# DSP_R.net
KiCad netlist of a schematic drawn in Altium Designer
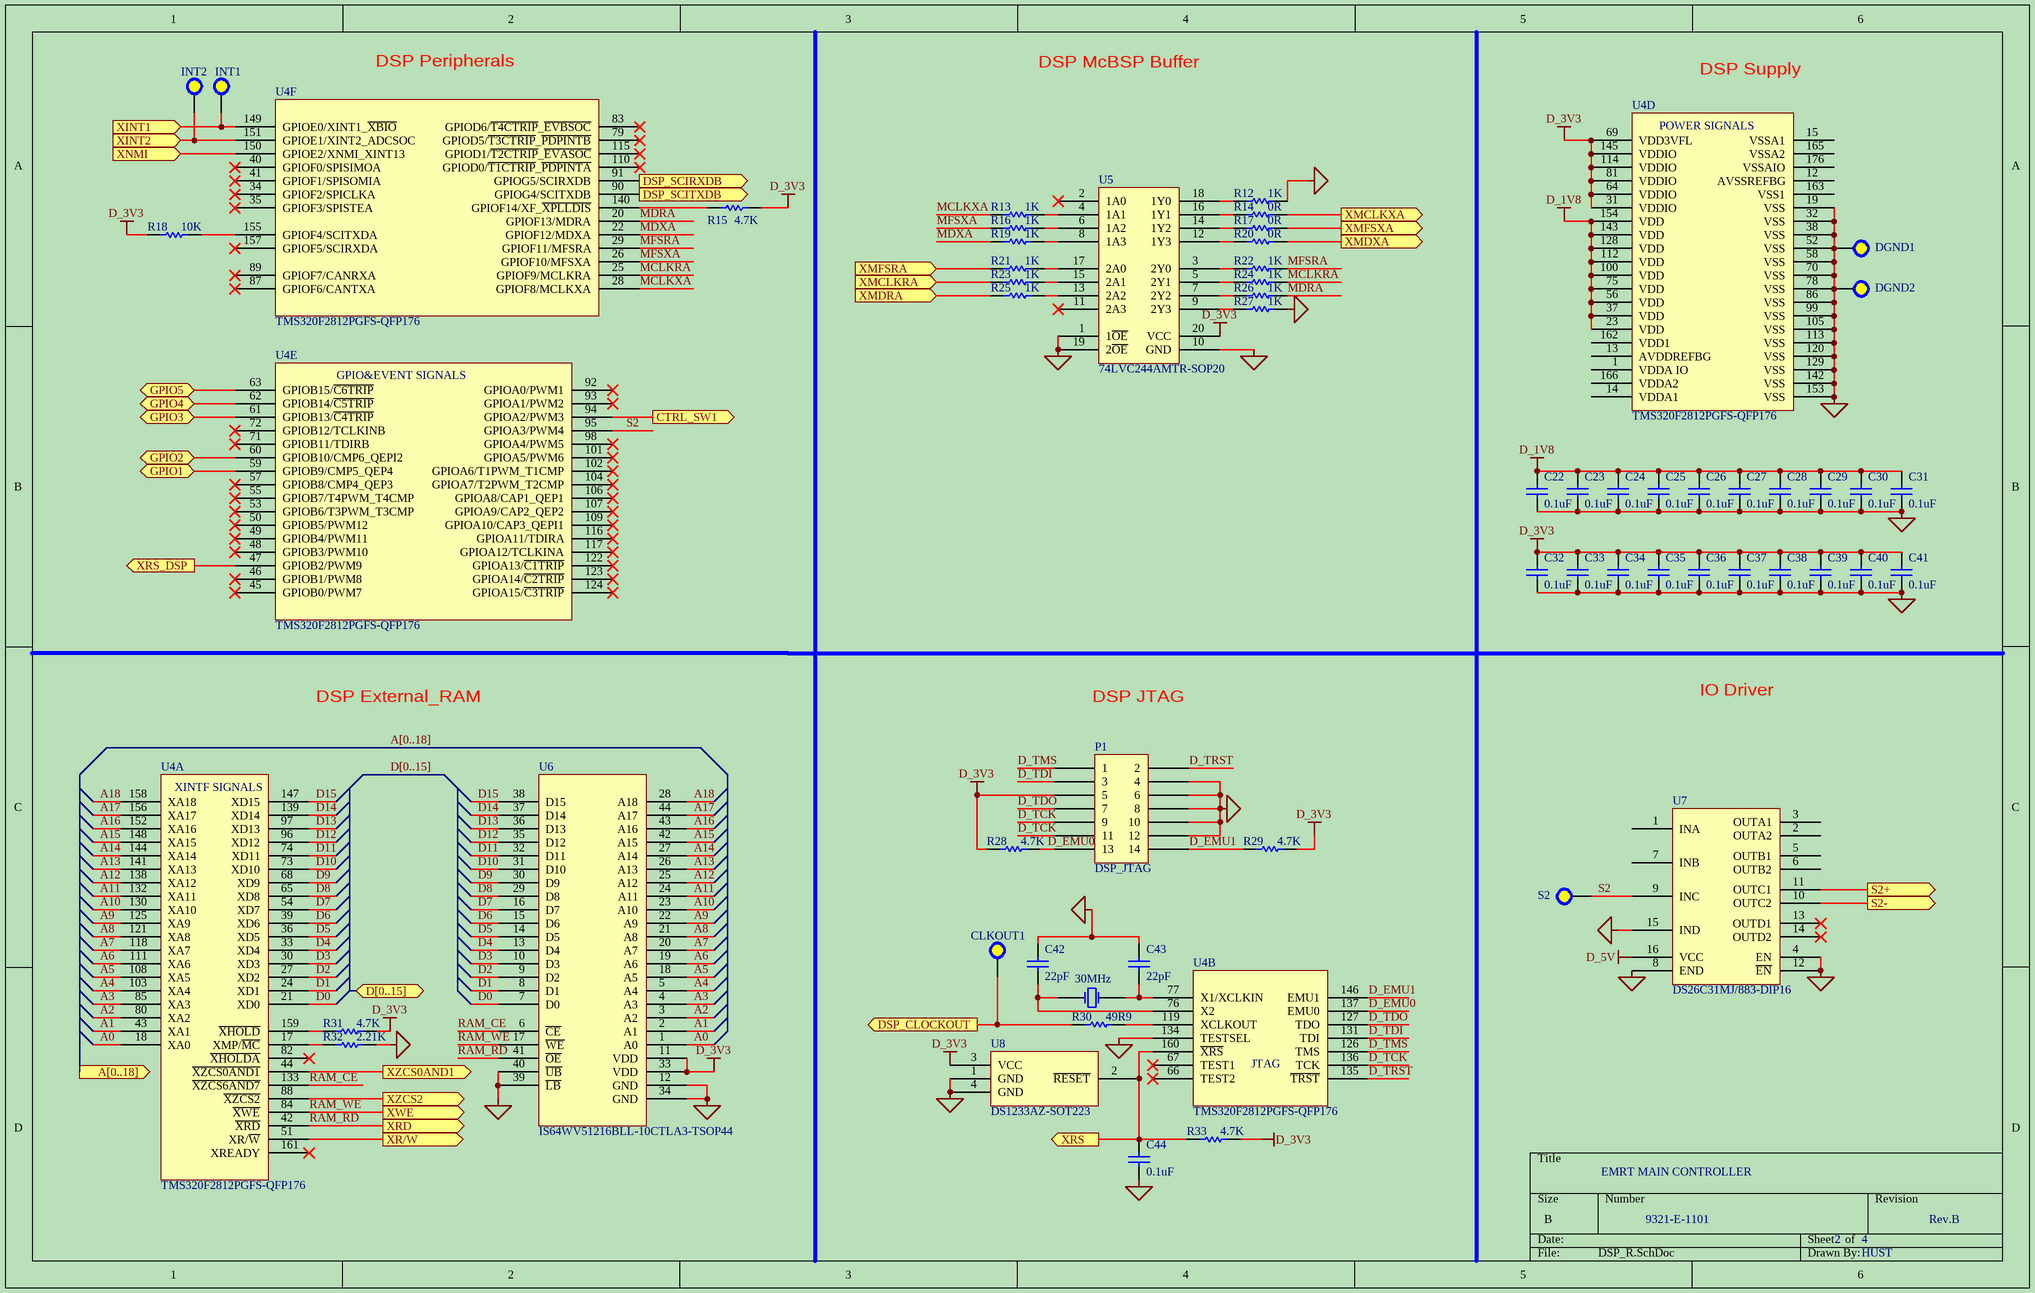
[diagram p0: DSP_R.SchDoc]

(export (version "E")
  (design (tool "Eeschema 10.0.6"))
  (components
    (comp (ref "C22")
      (value "0.1uF")
      (footprint "CAPS0805_57")
      (description "Capacitor")
      (fields (field (name "PART NUMBER") "Y20025084") (field (name "Comment") "Cap"))
      (libsource (lib "Cap") (part "Cap"))
    )
    (comp (ref "C23")
      (value "0.1uF")
      (footprint "CAPS0805_57")
      (description "Capacitor")
      (fields (field (name "PART NUMBER") "Y20025084") (field (name "Comment") "Cap"))
      (libsource (lib "Cap") (part "Cap"))
    )
    (comp (ref "C24")
      (value "0.1uF")
      (footprint "CAPS0805_57")
      (description "Capacitor")
      (fields (field (name "PART NUMBER") "Y20025084") (field (name "Comment") "Cap"))
      (libsource (lib "Cap") (part "Cap"))
    )
    (comp (ref "C25")
      (value "0.1uF")
      (footprint "CAPS0805_57")
      (description "Capacitor")
      (fields (field (name "PART NUMBER") "Y20025084") (field (name "Comment") "Cap"))
      (libsource (lib "Cap") (part "Cap"))
    )
    (comp (ref "C26")
      (value "0.1uF")
      (footprint "CAPS0805_57")
      (description "Capacitor")
      (fields (field (name "PART NUMBER") "Y20025084") (field (name "Comment") "Cap"))
      (libsource (lib "Cap") (part "Cap"))
    )
    (comp (ref "C27")
      (value "0.1uF")
      (footprint "CAPS0805_57")
      (description "Capacitor")
      (fields (field (name "PART NUMBER") "Y20025084") (field (name "Comment") "Cap"))
      (libsource (lib "Cap") (part "Cap"))
    )
    (comp (ref "C28")
      (value "0.1uF")
      (footprint "CAPS0805_57")
      (description "Capacitor")
      (fields (field (name "PART NUMBER") "Y20025084") (field (name "Comment") "Cap"))
      (libsource (lib "Cap") (part "Cap"))
    )
    (comp (ref "C29")
      (value "0.1uF")
      (footprint "CAPS0805_57")
      (description "Capacitor")
      (fields (field (name "PART NUMBER") "Y20025084") (field (name "Comment") "Cap"))
      (libsource (lib "Cap") (part "Cap"))
    )
    (comp (ref "C30")
      (value "0.1uF")
      (footprint "CAPS0805_57")
      (description "Capacitor")
      (fields (field (name "PART NUMBER") "Y20025084") (field (name "Comment") "Cap"))
      (libsource (lib "Cap") (part "Cap"))
    )
    (comp (ref "C31")
      (value "0.1uF")
      (footprint "CAPS0805_57")
      (description "Capacitor")
      (fields (field (name "PART NUMBER") "Y20025084") (field (name "Comment") "Cap"))
      (libsource (lib "Cap") (part "Cap"))
    )
    (comp (ref "C32")
      (value "0.1uF")
      (footprint "CAPS0805_57")
      (description "Capacitor")
      (fields (field (name "PART NUMBER") "Y20025084") (field (name "Comment") "Cap"))
      (libsource (lib "Cap") (part "Cap"))
    )
    (comp (ref "C33")
      (value "0.1uF")
      (footprint "CAPS0805_57")
      (description "Capacitor")
      (fields (field (name "PART NUMBER") "Y20025084") (field (name "Comment") "Cap"))
      (libsource (lib "Cap") (part "Cap"))
    )
    (comp (ref "C34")
      (value "0.1uF")
      (footprint "CAPS0805_57")
      (description "Capacitor")
      (fields (field (name "PART NUMBER") "Y20025084") (field (name "Comment") "Cap"))
      (libsource (lib "Cap") (part "Cap"))
    )
    (comp (ref "C35")
      (value "0.1uF")
      (footprint "CAPS0805_57")
      (description "Capacitor")
      (fields (field (name "PART NUMBER") "Y20025084") (field (name "Comment") "Cap"))
      (libsource (lib "Cap") (part "Cap"))
    )
    (comp (ref "C36")
      (value "0.1uF")
      (footprint "CAPS0805_57")
      (description "Capacitor")
      (fields (field (name "PART NUMBER") "Y20025084") (field (name "Comment") "Cap"))
      (libsource (lib "Cap") (part "Cap"))
    )
    (comp (ref "C37")
      (value "0.1uF")
      (footprint "CAPS0805_57")
      (description "Capacitor")
      (fields (field (name "PART NUMBER") "Y20025084") (field (name "Comment") "Cap"))
      (libsource (lib "Cap") (part "Cap"))
    )
    (comp (ref "C38")
      (value "0.1uF")
      (footprint "CAPS0805_57")
      (description "Capacitor")
      (fields (field (name "PART NUMBER") "Y20025084") (field (name "Comment") "Cap"))
      (libsource (lib "Cap") (part "Cap"))
    )
    (comp (ref "C39")
      (value "0.1uF")
      (footprint "CAPS0805_57")
      (description "Capacitor")
      (fields (field (name "PART NUMBER") "Y20025084") (field (name "Comment") "Cap"))
      (libsource (lib "Cap") (part "Cap"))
    )
    (comp (ref "C40")
      (value "0.1uF")
      (footprint "CAPS0805_57")
      (description "Capacitor")
      (fields (field (name "PART NUMBER") "Y20025084") (field (name "Comment") "Cap"))
      (libsource (lib "Cap") (part "Cap"))
    )
    (comp (ref "C41")
      (value "0.1uF")
      (footprint "CAPS0805_57")
      (description "Capacitor")
      (fields (field (name "PART NUMBER") "Y20025084") (field (name "Comment") "Cap"))
      (libsource (lib "Cap") (part "Cap"))
    )
    (comp (ref "C42")
      (value "22pF")
      (footprint "CAPS0805_57")
      (description "Capacitor")
      (fields (field (name "PART NUMBER") "Y20025084") (field (name "Comment") "Cap"))
      (libsource (lib "Cap") (part "Cap"))
    )
    (comp (ref "C43")
      (value "22pF")
      (footprint "CAPS0805_57")
      (description "Capacitor")
      (fields (field (name "PART NUMBER") "Y20025084") (field (name "Comment") "Cap"))
      (libsource (lib "Cap") (part "Cap"))
    )
    (comp (ref "C44")
      (value "0.1uF")
      (footprint "CAPS0805_57")
      (description "Capacitor")
      (fields (field (name "PART NUMBER") "Y20025084") (field (name "Comment") "Cap"))
      (libsource (lib "Cap") (part "Cap"))
    )
    (comp (ref "CLKOUT1")
      (value "TEST_SMALL")
      (footprint "test_small")
      (libsource (lib "srj") (part "TEST_SMALL"))
    )
    (comp (ref "DGND1")
      (value "TST_LARGE")
      (footprint "test_large")
      (libsource (lib "srj") (part "TEST_LARGE"))
    )
    (comp (ref "DGND2")
      (value "TST_LARGE")
      (footprint "test_large")
      (libsource (lib "srj") (part "TEST_LARGE"))
    )
    (comp (ref "INT1")
      (value "TEST_SMALL")
      (footprint "test_small")
      (libsource (lib "srj") (part "TEST_SMALL"))
    )
    (comp (ref "INT2")
      (value "TEST_SMALL")
      (footprint "test_small")
      (libsource (lib "srj") (part "TEST_SMALL"))
    )
    (comp (ref "P1")
      (value "DSP_JTAG")
      (footprint "HDR2X7")
      (libsource (lib "MainController-HT") (part "DSP_JTAG"))
    )
    (comp (ref "R12")
      (value "1K")
      (footprint "RESS0805")
      (description "Semiconductor Resistor")
      (fields
        (field (name "MANUFACTURER") "Generic Components")
        (field (name "Comment") "Res")
        (field (name "PUBLISHER") "Altium Hobart Technology Centre")
      )
      (libsource (lib "EMRT MAIN CONTROLLER") (part "Res"))
    )
    (comp (ref "R13")
      (value "1K")
      (footprint "RESS0805")
      (description "Semiconductor Resistor")
      (fields
        (field (name "MANUFACTURER") "Generic Components")
        (field (name "Comment") "Res")
        (field (name "PUBLISHER") "Altium Hobart Technology Centre")
      )
      (libsource (lib "EMRT MAIN CONTROLLER") (part "Res"))
    )
    (comp (ref "R14")
      (value "0R")
      (footprint "RESS0805")
      (description "Semiconductor Resistor")
      (fields
        (field (name "MANUFACTURER") "Generic Components")
        (field (name "Comment") "Res")
        (field (name "PUBLISHER") "Altium Hobart Technology Centre")
      )
      (libsource (lib "EMRT MAIN CONTROLLER") (part "Res"))
    )
    (comp (ref "R15")
      (value "4.7K")
      (footprint "RESS0805")
      (description "Semiconductor Resistor")
      (fields
        (field (name "MANUFACTURER") "Generic Components")
        (field (name "Comment") "Res")
        (field (name "PUBLISHER") "Altium Hobart Technology Centre")
      )
      (libsource (lib "EMRT MAIN CONTROLLER") (part "Res"))
    )
    (comp (ref "R16")
      (value "1K")
      (footprint "RESS0805")
      (description "Semiconductor Resistor")
      (fields
        (field (name "MANUFACTURER") "Generic Components")
        (field (name "Comment") "Res")
        (field (name "PUBLISHER") "Altium Hobart Technology Centre")
      )
      (libsource (lib "EMRT MAIN CONTROLLER") (part "Res"))
    )
    (comp (ref "R17")
      (value "0R")
      (footprint "RESS0805")
      (description "Semiconductor Resistor")
      (fields
        (field (name "MANUFACTURER") "Generic Components")
        (field (name "Comment") "Res")
        (field (name "PUBLISHER") "Altium Hobart Technology Centre")
      )
      (libsource (lib "EMRT MAIN CONTROLLER") (part "Res"))
    )
    (comp (ref "R18")
      (value "10K")
      (footprint "RESS0805")
      (description "Semiconductor Resistor")
      (fields
        (field (name "MANUFACTURER") "Generic Components")
        (field (name "Comment") "Res")
        (field (name "PUBLISHER") "Altium Hobart Technology Centre")
      )
      (libsource (lib "EMRT MAIN CONTROLLER") (part "Res"))
    )
    (comp (ref "R19")
      (value "1K")
      (footprint "RESS0805")
      (description "Semiconductor Resistor")
      (fields
        (field (name "MANUFACTURER") "Generic Components")
        (field (name "Comment") "Res")
        (field (name "PUBLISHER") "Altium Hobart Technology Centre")
      )
      (libsource (lib "EMRT MAIN CONTROLLER") (part "Res"))
    )
    (comp (ref "R20")
      (value "0R")
      (footprint "RESS0805")
      (description "Semiconductor Resistor")
      (fields
        (field (name "MANUFACTURER") "Generic Components")
        (field (name "Comment") "Res")
        (field (name "PUBLISHER") "Altium Hobart Technology Centre")
      )
      (libsource (lib "EMRT MAIN CONTROLLER") (part "Res"))
    )
    (comp (ref "R21")
      (value "1K")
      (footprint "RESS0805")
      (description "Semiconductor Resistor")
      (fields
        (field (name "MANUFACTURER") "Generic Components")
        (field (name "Comment") "Res")
        (field (name "PUBLISHER") "Altium Hobart Technology Centre")
      )
      (libsource (lib "EMRT MAIN CONTROLLER") (part "Res"))
    )
    (comp (ref "R22")
      (value "1K")
      (footprint "RESS0805")
      (description "Semiconductor Resistor")
      (fields
        (field (name "MANUFACTURER") "Generic Components")
        (field (name "Comment") "Res")
        (field (name "PUBLISHER") "Altium Hobart Technology Centre")
      )
      (libsource (lib "EMRT MAIN CONTROLLER") (part "Res"))
    )
    (comp (ref "R23")
      (value "1K")
      (footprint "RESS0805")
      (description "Semiconductor Resistor")
      (fields
        (field (name "MANUFACTURER") "Generic Components")
        (field (name "Comment") "Res")
        (field (name "PUBLISHER") "Altium Hobart Technology Centre")
      )
      (libsource (lib "EMRT MAIN CONTROLLER") (part "Res"))
    )
    (comp (ref "R24")
      (value "1K")
      (footprint "RESS0805")
      (description "Semiconductor Resistor")
      (fields
        (field (name "MANUFACTURER") "Generic Components")
        (field (name "Comment") "Res")
        (field (name "PUBLISHER") "Altium Hobart Technology Centre")
      )
      (libsource (lib "EMRT MAIN CONTROLLER") (part "Res"))
    )
    (comp (ref "R25")
      (value "1K")
      (footprint "RESS0805")
      (description "Semiconductor Resistor")
      (fields
        (field (name "MANUFACTURER") "Generic Components")
        (field (name "Comment") "Res")
        (field (name "PUBLISHER") "Altium Hobart Technology Centre")
      )
      (libsource (lib "EMRT MAIN CONTROLLER") (part "Res"))
    )
    (comp (ref "R26")
      (value "1K")
      (footprint "RESS0805")
      (description "Semiconductor Resistor")
      (fields
        (field (name "MANUFACTURER") "Generic Components")
        (field (name "Comment") "Res")
        (field (name "PUBLISHER") "Altium Hobart Technology Centre")
      )
      (libsource (lib "EMRT MAIN CONTROLLER") (part "Res"))
    )
    (comp (ref "R27")
      (value "1K")
      (footprint "RESS0805")
      (description "Semiconductor Resistor")
      (fields
        (field (name "MANUFACTURER") "Generic Components")
        (field (name "Comment") "Res")
        (field (name "PUBLISHER") "Altium Hobart Technology Centre")
      )
      (libsource (lib "EMRT MAIN CONTROLLER") (part "Res"))
    )
    (comp (ref "R28")
      (value "4.7K")
      (footprint "RESS0805")
      (description "Semiconductor Resistor")
      (fields
        (field (name "MANUFACTURER") "Generic Components")
        (field (name "Comment") "Res")
        (field (name "PUBLISHER") "Altium Hobart Technology Centre")
      )
      (libsource (lib "EMRT MAIN CONTROLLER") (part "Res"))
    )
    (comp (ref "R29")
      (value "4.7K")
      (footprint "RESS0805")
      (description "Semiconductor Resistor")
      (fields
        (field (name "MANUFACTURER") "Generic Components")
        (field (name "Comment") "Res")
        (field (name "PUBLISHER") "Altium Hobart Technology Centre")
      )
      (libsource (lib "EMRT MAIN CONTROLLER") (part "Res"))
    )
    (comp (ref "R30")
      (value "49R9")
      (footprint "RESS0805")
      (description "Semiconductor Resistor")
      (fields
        (field (name "MANUFACTURER") "Generic Components")
        (field (name "Comment") "Res")
        (field (name "PUBLISHER") "Altium Hobart Technology Centre")
      )
      (libsource (lib "EMRT MAIN CONTROLLER") (part "Res"))
    )
    (comp (ref "R31")
      (value "4.7K")
      (footprint "RESS0805")
      (description "Semiconductor Resistor")
      (fields
        (field (name "MANUFACTURER") "Generic Components")
        (field (name "Comment") "Res")
        (field (name "PUBLISHER") "Altium Hobart Technology Centre")
      )
      (libsource (lib "EMRT MAIN CONTROLLER") (part "Res"))
    )
    (comp (ref "R32")
      (value "2.21K")
      (footprint "RESS0805")
      (description "Semiconductor Resistor")
      (fields
        (field (name "MANUFACTURER") "Generic Components")
        (field (name "Comment") "Res")
        (field (name "PUBLISHER") "Altium Hobart Technology Centre")
      )
      (libsource (lib "EMRT MAIN CONTROLLER") (part "Res"))
    )
    (comp (ref "R33")
      (value "4.7K")
      (footprint "RESS0805")
      (description "Semiconductor Resistor")
      (fields
        (field (name "MANUFACTURER") "Generic Components")
        (field (name "Comment") "Res")
        (field (name "PUBLISHER") "Altium Hobart Technology Centre")
      )
      (libsource (lib "EMRT MAIN CONTROLLER") (part "Res"))
    )
    (comp (ref "S2") (value "TST_LARGE") (footprint "test_large") (libsource (lib "srj") (part "TEST_LARGE")))
    (comp (ref "U4")
      (value "TMS320F2812PGFS-QFP176")
      (footprint "QFP176")
      (libsource (lib "srj") (part "TMS320F2812(176PIN)"))
    )
    (comp (ref "U5")
      (value "74LVC244AMTR-SOP20")
      (footprint "B-PDSO_20q1280×1030×265_p127")
      (libsource (lib "srj") (part "74LVC244AMTR"))
    )
    (comp (ref "U6")
      (value "IS64WV51216BLL-10CTLA3-TSOP44")
      (footprint "TSOP44")
      (libsource (lib "srj") (part "IS61LV51216"))
    )
    (comp (ref "U7")
      (value "DS26C31MJ/883-DIP16")
      (footprint "CDIP_16q785×305×200_d18_p100_i300")
      (libsource (lib "srj") (part "DS26LVC31"))
    )
    (comp (ref "U8")
      (value "DS1233AZ-SOT223")
      (footprint "PDSO_3q700×650×180_p230")
      (libsource (lib "srj") (part "DS1233AZ-15"))
    )
    (comp (ref "Y1")
      (value "XTAL")
      (footprint "XTALBCY_2q311×126×236_d13_p150")
      (description "Crystal Oscillator")
      (fields (field (name "ALTIUM_UNNAMED_1") "30MHz") (field (name "PUBLISHER") "Altium Limited"))
      (libsource (lib "Miscellaneous Devices") (part "XTAL"))
    )
  )
  (nets
    (net (code "1") (name "/A0") (class "Default")
      (node (ref "U4") (pin "18") (pinfunction "XA0_18") (pintype "passive"))
      (node (ref "U6") (pin "1") (pinfunction "A0_1") (pintype "passive"))
    )
    (net (code "2") (name "/A1") (class "Default")
      (node (ref "U4") (pin "43") (pinfunction "XA1_43") (pintype "passive"))
      (node (ref "U6") (pin "2") (pinfunction "A1_2") (pintype "passive"))
    )
    (net (code "3") (name "/A2") (class "Default")
      (node (ref "U4") (pin "80") (pinfunction "XA2_80") (pintype "passive"))
      (node (ref "U6") (pin "3") (pinfunction "A2_3") (pintype "passive"))
    )
    (net (code "4") (name "/A3") (class "Default")
      (node (ref "U4") (pin "85") (pinfunction "XA3_85") (pintype "passive"))
      (node (ref "U6") (pin "4") (pinfunction "A3_4") (pintype "passive"))
    )
    (net (code "5") (name "/A4") (class "Default")
      (node (ref "U4") (pin "103") (pinfunction "XA4_103") (pintype "passive"))
      (node (ref "U6") (pin "5") (pinfunction "A4_5") (pintype "passive"))
    )
    (net (code "6") (name "/A5") (class "Default")
      (node (ref "U4") (pin "108") (pinfunction "XA5_108") (pintype "passive"))
      (node (ref "U6") (pin "18") (pinfunction "A5_18") (pintype "passive"))
    )
    (net (code "7") (name "/A6") (class "Default")
      (node (ref "U4") (pin "111") (pinfunction "XA6_111") (pintype "passive"))
      (node (ref "U6") (pin "19") (pinfunction "A6_19") (pintype "passive"))
    )
    (net (code "8") (name "/A7") (class "Default")
      (node (ref "U4") (pin "118") (pinfunction "XA7_118") (pintype "passive"))
      (node (ref "U6") (pin "20") (pinfunction "A7_20") (pintype "passive"))
    )
    (net (code "9") (name "/A8") (class "Default")
      (node (ref "U4") (pin "121") (pinfunction "XA8_121") (pintype "passive"))
      (node (ref "U6") (pin "21") (pinfunction "A8_21") (pintype "passive"))
    )
    (net (code "10") (name "/A9") (class "Default")
      (node (ref "U4") (pin "125") (pinfunction "XA9_125") (pintype "passive"))
      (node (ref "U6") (pin "22") (pinfunction "A9_22") (pintype "passive"))
    )
    (net (code "11") (name "/A10") (class "Default")
      (node (ref "U4") (pin "130") (pinfunction "XA10_130") (pintype "passive"))
      (node (ref "U6") (pin "23") (pinfunction "A10_23") (pintype "passive"))
    )
    (net (code "12") (name "/A11") (class "Default")
      (node (ref "U4") (pin "132") (pinfunction "XA11_132") (pintype "passive"))
      (node (ref "U6") (pin "24") (pinfunction "A11_24") (pintype "passive"))
    )
    (net (code "13") (name "/A12") (class "Default")
      (node (ref "U4") (pin "138") (pinfunction "XA12_138") (pintype "passive"))
      (node (ref "U6") (pin "25") (pinfunction "A12_25") (pintype "passive"))
    )
    (net (code "14") (name "/A13") (class "Default")
      (node (ref "U4") (pin "141") (pinfunction "XA13_141") (pintype "passive"))
      (node (ref "U6") (pin "26") (pinfunction "A13_26") (pintype "passive"))
    )
    (net (code "15") (name "/A14") (class "Default")
      (node (ref "U4") (pin "144") (pinfunction "XA14_144") (pintype "passive"))
      (node (ref "U6") (pin "27") (pinfunction "A14_27") (pintype "passive"))
    )
    (net (code "16") (name "/A15") (class "Default")
      (node (ref "U4") (pin "148") (pinfunction "XA15_148") (pintype "passive"))
      (node (ref "U6") (pin "42") (pinfunction "A15_42") (pintype "passive"))
    )
    (net (code "17") (name "/A16") (class "Default")
      (node (ref "U4") (pin "152") (pinfunction "XA16_152") (pintype "passive"))
      (node (ref "U6") (pin "43") (pinfunction "A16_43") (pintype "passive"))
    )
    (net (code "18") (name "/A17") (class "Default")
      (node (ref "U4") (pin "156") (pinfunction "XA17_156") (pintype "passive"))
      (node (ref "U6") (pin "44") (pinfunction "A17_44") (pintype "passive"))
    )
    (net (code "19") (name "/A18") (class "Default")
      (node (ref "U4") (pin "158") (pinfunction "XA18_158") (pintype "passive"))
      (node (ref "U6") (pin "28") (pinfunction "A18_28") (pintype "passive"))
    )
    (net (code "21") (name "/CTRL_SW1") (class "Default")
      (node (ref "U4") (pin "94") (pinfunction "GPIOA2/PWM3_94") (pintype "passive"))
    )
    (net (code "22") (name "/D0") (class "Default")
      (node (ref "U4") (pin "21") (pinfunction "XD0_21") (pintype "passive"))
      (node (ref "U6") (pin "7") (pinfunction "D0_7") (pintype "passive"))
    )
    (net (code "23") (name "/D1") (class "Default")
      (node (ref "U4") (pin "24") (pinfunction "XD1_24") (pintype "passive"))
      (node (ref "U6") (pin "8") (pinfunction "D1_8") (pintype "passive"))
    )
    (net (code "24") (name "/D2") (class "Default")
      (node (ref "U4") (pin "27") (pinfunction "XD2_27") (pintype "passive"))
      (node (ref "U6") (pin "9") (pinfunction "D2_9") (pintype "passive"))
    )
    (net (code "25") (name "/D3") (class "Default")
      (node (ref "U4") (pin "30") (pinfunction "XD3_30") (pintype "passive"))
      (node (ref "U6") (pin "10") (pinfunction "D3_10") (pintype "passive"))
    )
    (net (code "26") (name "/D4") (class "Default")
      (node (ref "U4") (pin "33") (pinfunction "XD4_33") (pintype "passive"))
      (node (ref "U6") (pin "13") (pinfunction "D4_13") (pintype "passive"))
    )
    (net (code "27") (name "/D5") (class "Default")
      (node (ref "U4") (pin "36") (pinfunction "XD5_36") (pintype "passive"))
      (node (ref "U6") (pin "14") (pinfunction "D5_14") (pintype "passive"))
    )
    (net (code "28") (name "/D6") (class "Default")
      (node (ref "U4") (pin "39") (pinfunction "XD6_39") (pintype "passive"))
      (node (ref "U6") (pin "15") (pinfunction "D6_15") (pintype "passive"))
    )
    (net (code "29") (name "/D7") (class "Default")
      (node (ref "U4") (pin "54") (pinfunction "XD7_54") (pintype "passive"))
      (node (ref "U6") (pin "16") (pinfunction "D7_16") (pintype "passive"))
    )
    (net (code "30") (name "/D8") (class "Default")
      (node (ref "U4") (pin "65") (pinfunction "XD8_65") (pintype "passive"))
      (node (ref "U6") (pin "29") (pinfunction "D8_29") (pintype "passive"))
    )
    (net (code "31") (name "/D9") (class "Default")
      (node (ref "U4") (pin "68") (pinfunction "XD9_68") (pintype "passive"))
      (node (ref "U6") (pin "30") (pinfunction "D9_30") (pintype "passive"))
    )
    (net (code "32") (name "/D10") (class "Default")
      (node (ref "U4") (pin "73") (pinfunction "XD10_73") (pintype "passive"))
      (node (ref "U6") (pin "31") (pinfunction "D10_31") (pintype "passive"))
    )
    (net (code "33") (name "/D11") (class "Default")
      (node (ref "U4") (pin "74") (pinfunction "XD11_74") (pintype "passive"))
      (node (ref "U6") (pin "32") (pinfunction "D11_32") (pintype "passive"))
    )
    (net (code "34") (name "/D12") (class "Default")
      (node (ref "U4") (pin "96") (pinfunction "XD12_96") (pintype "passive"))
      (node (ref "U6") (pin "35") (pinfunction "D12_35") (pintype "passive"))
    )
    (net (code "35") (name "/D13") (class "Default")
      (node (ref "U4") (pin "97") (pinfunction "XD13_97") (pintype "passive"))
      (node (ref "U6") (pin "36") (pinfunction "D13_36") (pintype "passive"))
    )
    (net (code "36") (name "/D14") (class "Default")
      (node (ref "U4") (pin "139") (pinfunction "XD14_139") (pintype "passive"))
      (node (ref "U6") (pin "37") (pinfunction "D14_37") (pintype "passive"))
    )
    (net (code "37") (name "/D15") (class "Default")
      (node (ref "U4") (pin "147") (pinfunction "XD15_147") (pintype "passive"))
      (node (ref "U6") (pin "38") (pinfunction "D15_38") (pintype "passive"))
    )
    (net (code "38") (name "/DSP_CLOCKOUT") (class "Default")
      (node (ref "CLKOUT1") (pin "1") (pinfunction "1_1") (pintype "passive"))
      (node (ref "R30") (pin "2") (pinfunction "2_2") (pintype "passive"))
    )
    (net (code "39") (name "/DSP_SCIRXDB") (class "Default")
      (node (ref "U4") (pin "91") (pinfunction "GPIOG5/SCIRXDB_91") (pintype "passive"))
    )
    (net (code "40") (name "/DSP_SCITXDB") (class "Default")
      (node (ref "U4") (pin "90") (pinfunction "GPIOG4/SCITXDB_90") (pintype "passive"))
    )
    (net (code "42") (name "/D_EMU0") (class "Default")
      (node (ref "P1") (pin "13") (pinfunction "13_13") (pintype "passive"))
      (node (ref "R28") (pin "1") (pinfunction "1_1") (pintype "passive"))
      (node (ref "U4") (pin "137") (pinfunction "EMU0_137") (pintype "passive"))
    )
    (net (code "43") (name "/D_EMU1") (class "Default")
      (node (ref "P1") (pin "14") (pinfunction "14_14") (pintype "passive"))
      (node (ref "R29") (pin "2") (pinfunction "2_2") (pintype "passive"))
      (node (ref "U4") (pin "146") (pinfunction "EMU1_146") (pintype "passive"))
    )
    (net (code "44") (name "/D_TCK") (class "Default")
      (node (ref "P1") (pin "11") (pinfunction "11_11") (pintype "passive"))
      (node (ref "P1") (pin "9") (pinfunction "9_9") (pintype "passive"))
      (node (ref "U4") (pin "136") (pinfunction "TCK_136") (pintype "passive"))
    )
    (net (code "45") (name "/D_TDI") (class "Default")
      (node (ref "P1") (pin "3") (pinfunction "3_3") (pintype "passive"))
      (node (ref "U4") (pin "131") (pinfunction "TDI_131") (pintype "passive"))
    )
    (net (code "46") (name "/D_TDO") (class "Default")
      (node (ref "P1") (pin "7") (pinfunction "7_7") (pintype "passive"))
      (node (ref "U4") (pin "127") (pinfunction "TDO_127") (pintype "passive"))
    )
    (net (code "47") (name "/D_TMS") (class "Default")
      (node (ref "P1") (pin "1") (pinfunction "1_1") (pintype "passive"))
      (node (ref "U4") (pin "126") (pinfunction "TMS_126") (pintype "passive"))
    )
    (net (code "48") (name "/D_TRST") (class "Default")
      (node (ref "P1") (pin "2") (pinfunction "2_2") (pintype "passive"))
      (node (ref "U4") (pin "135") (pinfunction "~{TRST}_135") (pintype "passive"))
    )
    (net (code "49") (name "/GPIO1") (class "Default")
      (node (ref "U4") (pin "59") (pinfunction "GPIOB9/CMP5_QEP4_59") (pintype "passive"))
    )
    (net (code "50") (name "/GPIO2") (class "Default")
      (node (ref "U4") (pin "60") (pinfunction "GPIOB10/CMP6_QEPI2_60") (pintype "passive"))
    )
    (net (code "51") (name "/GPIO3") (class "Default")
      (node (ref "U4") (pin "61") (pinfunction "GPIOB13/~{C4TRIP}_61") (pintype "passive"))
    )
    (net (code "52") (name "/GPIO4") (class "Default")
      (node (ref "U4") (pin "62") (pinfunction "GPIOB14/~{C5TRIP}_62") (pintype "passive"))
    )
    (net (code "53") (name "/GPIO5") (class "Default")
      (node (ref "U4") (pin "63") (pinfunction "GPIOB15/~{C6TRIP}_63") (pintype "passive"))
    )
    (net (code "54") (name "/MCLKRA") (class "Default")
      (node (ref "R24") (pin "1") (pinfunction "1_1") (pintype "passive"))
      (node (ref "U4") (pin "25") (pinfunction "GPIOF9/MCLKRA_25") (pintype "passive"))
    )
    (net (code "55") (name "/MCLKXA") (class "Default")
      (node (ref "R13") (pin "2") (pinfunction "2_2") (pintype "passive"))
      (node (ref "U4") (pin "28") (pinfunction "GPIOF8/MCLKXA_28") (pintype "passive"))
    )
    (net (code "56") (name "/MDRA") (class "Default")
      (node (ref "R26") (pin "1") (pinfunction "1_1") (pintype "passive"))
      (node (ref "U4") (pin "20") (pinfunction "GPIOF13/MDRA_20") (pintype "passive"))
    )
    (net (code "57") (name "/MDXA") (class "Default")
      (node (ref "R19") (pin "2") (pinfunction "2_2") (pintype "passive"))
      (node (ref "U4") (pin "22") (pinfunction "GPIOF12/MDXA_22") (pintype "passive"))
    )
    (net (code "58") (name "/MFSRA") (class "Default")
      (node (ref "R22") (pin "1") (pinfunction "1_1") (pintype "passive"))
      (node (ref "U4") (pin "29") (pinfunction "GPIOF11/MFSRA_29") (pintype "passive"))
    )
    (net (code "59") (name "/MFSXA") (class "Default")
      (node (ref "R16") (pin "2") (pinfunction "2_2") (pintype "passive"))
      (node (ref "U4") (pin "26") (pinfunction "GPIOF10/MFSXA_26") (pintype "passive"))
    )
    (net (code "60") (name "/RAM_CE") (class "Default")
      (node (ref "U4") (pin "133") (pinfunction "~{XZCS6AND7}_133") (pintype "passive"))
      (node (ref "U6") (pin "6") (pinfunction "~{CE}_6") (pintype "passive"))
    )
    (net (code "61") (name "/RAM_RD") (class "Default")
      (node (ref "U4") (pin "42") (pinfunction "~{XRD}_42") (pintype "passive"))
      (node (ref "U6") (pin "41") (pinfunction "~{OE}_41") (pintype "passive"))
    )
    (net (code "62") (name "/RAM_WE") (class "Default")
      (node (ref "U4") (pin "84") (pinfunction "~{XWE}_84") (pintype "passive"))
      (node (ref "U6") (pin "17") (pinfunction "~{WE}_17") (pintype "passive"))
    )
    (net (code "63") (name "/S2") (class "Default")
      (node (ref "S2") (pin "1") (pinfunction "1_1") (pintype "passive"))
      (node (ref "U4") (pin "95") (pinfunction "GPIOA3/PWM4_95") (pintype "passive"))
      (node (ref "U7") (pin "9") (pinfunction "INC_9") (pintype "passive"))
    )
    (net (code "64") (name "/S2+") (class "Default")
      (node (ref "U7") (pin "11") (pinfunction "OUTC1_11") (pintype "passive"))
    )
    (net (code "65") (name "/S2-") (class "Default")
      (node (ref "U7") (pin "10") (pinfunction "OUTC2_10") (pintype "passive"))
    )
    (net (code "66") (name "/XINT1") (class "Default")
      (node (ref "INT1") (pin "1") (pinfunction "1_1") (pintype "passive"))
      (node (ref "U4") (pin "149") (pinfunction "GPIOE0/XINT1_~{XBIO}_149") (pintype "passive"))
    )
    (net (code "67") (name "/XINT2") (class "Default")
      (node (ref "INT2") (pin "1") (pinfunction "1_1") (pintype "passive"))
      (node (ref "U4") (pin "151") (pinfunction "GPIOE1/XINT2_ADCSOC_151") (pintype "passive"))
    )
    (net (code "68") (name "/XMCLKRA") (class "Default")
      (node (ref "R23") (pin "2") (pinfunction "2_2") (pintype "passive"))
    )
    (net (code "69") (name "/XMCLKXA") (class "Default")
      (node (ref "R14") (pin "1") (pinfunction "1_1") (pintype "passive"))
    )
    (net (code "70") (name "/XMDRA") (class "Default")
      (node (ref "R25") (pin "2") (pinfunction "2_2") (pintype "passive"))
    )
    (net (code "71") (name "/XMDXA") (class "Default")
      (node (ref "R20") (pin "1") (pinfunction "1_1") (pintype "passive"))
    )
    (net (code "72") (name "/XMFSRA") (class "Default")
      (node (ref "R21") (pin "2") (pinfunction "2_2") (pintype "passive"))
    )
    (net (code "73") (name "/XMFSXA") (class "Default")
      (node (ref "R17") (pin "1") (pinfunction "1_1") (pintype "passive"))
    )
    (net (code "74") (name "/XNMI") (class "Default")
      (node (ref "U4") (pin "150") (pinfunction "GPIOE2/XNMI_XINT13_150") (pintype "passive"))
    )
    (net (code "75") (name "/XRS") (class "Default")
      (node (ref "C44") (pin "2") (pinfunction "2_2") (pintype "passive"))
      (node (ref "R33") (pin "2") (pinfunction "2_2") (pintype "passive"))
      (node (ref "U4") (pin "160") (pinfunction "~{XRS}_160") (pintype "passive"))
      (node (ref "U8") (pin "2") (pinfunction "~{RESET}_2") (pintype "passive"))
    )
    (net (code "76") (name "/XRS_DSP") (class "Default")
      (node (ref "U4") (pin "47") (pinfunction "GPIOB2/PWM9_47") (pintype "passive"))
    )
    (net (code "77") (name "/XR{slash}W") (class "Default")
      (node (ref "U4") (pin "51") (pinfunction "XR/~{W}_51") (pintype "passive"))
    )
    (net (code "78") (name "/XZCS0AND1") (class "Default")
      (node (ref "U4") (pin "44") (pinfunction "~{XZCS0AND1}_44") (pintype "passive"))
    )
    (net (code "79") (name "/XZCS2") (class "Default")
      (node (ref "U4") (pin "88") (pinfunction "~{XZCS2}_88") (pintype "passive"))
    )
    (net (code "80") (name "DGND") (class "Default")
      (node (ref "C22") (pin "1") (pinfunction "1_1") (pintype "passive"))
      (node (ref "C23") (pin "1") (pinfunction "1_1") (pintype "passive"))
      (node (ref "C24") (pin "1") (pinfunction "1_1") (pintype "passive"))
      (node (ref "C25") (pin "1") (pinfunction "1_1") (pintype "passive"))
      (node (ref "C26") (pin "1") (pinfunction "1_1") (pintype "passive"))
      (node (ref "C27") (pin "1") (pinfunction "1_1") (pintype "passive"))
      (node (ref "C28") (pin "1") (pinfunction "1_1") (pintype "passive"))
      (node (ref "C29") (pin "1") (pinfunction "1_1") (pintype "passive"))
      (node (ref "C30") (pin "1") (pinfunction "1_1") (pintype "passive"))
      (node (ref "C31") (pin "1") (pinfunction "1_1") (pintype "passive"))
      (node (ref "C32") (pin "1") (pinfunction "1_1") (pintype "passive"))
      (node (ref "C33") (pin "1") (pinfunction "1_1") (pintype "passive"))
      (node (ref "C34") (pin "1") (pinfunction "1_1") (pintype "passive"))
      (node (ref "C35") (pin "1") (pinfunction "1_1") (pintype "passive"))
      (node (ref "C36") (pin "1") (pinfunction "1_1") (pintype "passive"))
      (node (ref "C37") (pin "1") (pinfunction "1_1") (pintype "passive"))
      (node (ref "C38") (pin "1") (pinfunction "1_1") (pintype "passive"))
      (node (ref "C39") (pin "1") (pinfunction "1_1") (pintype "passive"))
      (node (ref "C40") (pin "1") (pinfunction "1_1") (pintype "passive"))
      (node (ref "C41") (pin "1") (pinfunction "1_1") (pintype "passive"))
      (node (ref "C42") (pin "2") (pinfunction "2_2") (pintype "passive"))
      (node (ref "C43") (pin "2") (pinfunction "2_2") (pintype "passive"))
      (node (ref "C44") (pin "1") (pinfunction "1_1") (pintype "passive"))
      (node (ref "DGND1") (pin "1") (pinfunction "1_1") (pintype "passive"))
      (node (ref "DGND2") (pin "1") (pinfunction "1_1") (pintype "passive"))
      (node (ref "P1") (pin "10") (pinfunction "10_10") (pintype "passive"))
      (node (ref "P1") (pin "12") (pinfunction "12_12") (pintype "passive"))
      (node (ref "P1") (pin "4") (pinfunction "4_4") (pintype "passive"))
      (node (ref "P1") (pin "6") (pinfunction "6_6") (pintype "passive"))
      (node (ref "P1") (pin "8") (pinfunction "8_8") (pintype "passive"))
      (node (ref "R12") (pin "1") (pinfunction "1_1") (pintype "passive"))
      (node (ref "R27") (pin "1") (pinfunction "1_1") (pintype "passive"))
      (node (ref "R32") (pin "1") (pinfunction "1_1") (pintype "passive"))
      (node (ref "U4") (pin "105") (pinfunction "VSS_105") (pintype "passive"))
      (node (ref "U4") (pin "113") (pinfunction "VSS_113") (pintype "passive"))
      (node (ref "U4") (pin "120") (pinfunction "VSS_120") (pintype "passive"))
      (node (ref "U4") (pin "129") (pinfunction "VSS_129") (pintype "passive"))
      (node (ref "U4") (pin "134") (pinfunction "TESTSEL_134") (pintype "passive"))
      (node (ref "U4") (pin "142") (pinfunction "VSS_142") (pintype "passive"))
      (node (ref "U4") (pin "153") (pinfunction "VSS_153") (pintype "passive"))
      (node (ref "U4") (pin "19") (pinfunction "VSS_19") (pintype "passive"))
      (node (ref "U4") (pin "32") (pinfunction "VSS_32") (pintype "passive"))
      (node (ref "U4") (pin "38") (pinfunction "VSS_38") (pintype "passive"))
      (node (ref "U4") (pin "52") (pinfunction "VSS_52") (pintype "passive"))
      (node (ref "U4") (pin "58") (pinfunction "VSS_58") (pintype "passive"))
      (node (ref "U4") (pin "70") (pinfunction "VSS_70") (pintype "passive"))
      (node (ref "U4") (pin "78") (pinfunction "VSS_78") (pintype "passive"))
      (node (ref "U4") (pin "86") (pinfunction "VSS_86") (pintype "passive"))
      (node (ref "U4") (pin "99") (pinfunction "VSS_99") (pintype "passive"))
      (node (ref "U5") (pin "1") (pinfunction "1~{OE}_1") (pintype "passive"))
      (node (ref "U5") (pin "10") (pinfunction "GND_10") (pintype "passive"))
      (node (ref "U5") (pin "19") (pinfunction "2~{OE}_19") (pintype "passive"))
      (node (ref "U6") (pin "12") (pinfunction "GND_12") (pintype "passive"))
      (node (ref "U6") (pin "34") (pinfunction "GND_34") (pintype "passive"))
      (node (ref "U6") (pin "39") (pinfunction "~{LB}_39") (pintype "passive"))
      (node (ref "U6") (pin "40") (pinfunction "~{UB}_40") (pintype "passive"))
      (node (ref "U7") (pin "12") (pinfunction "~{EN}_12") (pintype "passive"))
      (node (ref "U7") (pin "15") (pinfunction "IND_15") (pintype "passive"))
      (node (ref "U7") (pin "4") (pinfunction "EN_4") (pintype "passive"))
      (node (ref "U7") (pin "8") (pinfunction "END_8") (pintype "passive"))
      (node (ref "U8") (pin "1") (pinfunction "GND_1") (pintype "passive"))
      (node (ref "U8") (pin "4") (pinfunction "GND_4") (pintype "passive"))
    )
    (net (code "81") (name "D_1V8") (class "Default")
      (node (ref "C22") (pin "2") (pinfunction "2_2") (pintype "passive"))
      (node (ref "C23") (pin "2") (pinfunction "2_2") (pintype "passive"))
      (node (ref "C24") (pin "2") (pinfunction "2_2") (pintype "passive"))
      (node (ref "C25") (pin "2") (pinfunction "2_2") (pintype "passive"))
      (node (ref "C26") (pin "2") (pinfunction "2_2") (pintype "passive"))
      (node (ref "C27") (pin "2") (pinfunction "2_2") (pintype "passive"))
      (node (ref "C28") (pin "2") (pinfunction "2_2") (pintype "passive"))
      (node (ref "C29") (pin "2") (pinfunction "2_2") (pintype "passive"))
      (node (ref "C30") (pin "2") (pinfunction "2_2") (pintype "passive"))
      (node (ref "C31") (pin "2") (pinfunction "2_2") (pintype "passive"))
      (node (ref "U4") (pin "100") (pinfunction "VDD_100") (pintype "passive"))
      (node (ref "U4") (pin "112") (pinfunction "VDD_112") (pintype "passive"))
      (node (ref "U4") (pin "128") (pinfunction "VDD_128") (pintype "passive"))
      (node (ref "U4") (pin "143") (pinfunction "VDD_143") (pintype "passive"))
      (node (ref "U4") (pin "154") (pinfunction "VDD_154") (pintype "passive"))
      (node (ref "U4") (pin "23") (pinfunction "VDD_23") (pintype "passive"))
      (node (ref "U4") (pin "37") (pinfunction "VDD_37") (pintype "passive"))
      (node (ref "U4") (pin "56") (pinfunction "VDD_56") (pintype "passive"))
      (node (ref "U4") (pin "75") (pinfunction "VDD_75") (pintype "passive"))
    )
    (net (code "82") (name "D_3V3") (class "Default")
      (node (ref "C32") (pin "2") (pinfunction "2_2") (pintype "passive"))
      (node (ref "C33") (pin "2") (pinfunction "2_2") (pintype "passive"))
      (node (ref "C34") (pin "2") (pinfunction "2_2") (pintype "passive"))
      (node (ref "C35") (pin "2") (pinfunction "2_2") (pintype "passive"))
      (node (ref "C36") (pin "2") (pinfunction "2_2") (pintype "passive"))
      (node (ref "C37") (pin "2") (pinfunction "2_2") (pintype "passive"))
      (node (ref "C38") (pin "2") (pinfunction "2_2") (pintype "passive"))
      (node (ref "C39") (pin "2") (pinfunction "2_2") (pintype "passive"))
      (node (ref "C40") (pin "2") (pinfunction "2_2") (pintype "passive"))
      (node (ref "C41") (pin "2") (pinfunction "2_2") (pintype "passive"))
      (node (ref "P1") (pin "5") (pinfunction "5_5") (pintype "passive"))
      (node (ref "R15") (pin "1") (pinfunction "1_1") (pintype "passive"))
      (node (ref "R18") (pin "2") (pinfunction "2_2") (pintype "passive"))
      (node (ref "R28") (pin "2") (pinfunction "2_2") (pintype "passive"))
      (node (ref "R29") (pin "1") (pinfunction "1_1") (pintype "passive"))
      (node (ref "R31") (pin "1") (pinfunction "1_1") (pintype "passive"))
      (node (ref "R33") (pin "1") (pinfunction "1_1") (pintype "passive"))
      (node (ref "U4") (pin "114") (pinfunction "VDDIO_114") (pintype "passive"))
      (node (ref "U4") (pin "145") (pinfunction "VDDIO_145") (pintype "passive"))
      (node (ref "U4") (pin "31") (pinfunction "VDDIO_31") (pintype "passive"))
      (node (ref "U4") (pin "64") (pinfunction "VDDIO_64") (pintype "passive"))
      (node (ref "U4") (pin "69") (pinfunction "VDD3VFL_69") (pintype "passive"))
      (node (ref "U4") (pin "81") (pinfunction "VDDIO_81") (pintype "passive"))
      (node (ref "U5") (pin "20") (pinfunction "VCC_20") (pintype "passive"))
      (node (ref "U6") (pin "11") (pinfunction "VDD_11") (pintype "passive"))
      (node (ref "U6") (pin "33") (pinfunction "VDD_33") (pintype "passive"))
      (node (ref "U8") (pin "3") (pinfunction "VCC_3") (pintype "passive"))
    )
    (net (code "83") (name "D_5V") (class "Default")
      (node (ref "U7") (pin "16") (pinfunction "VCC_16") (pintype "passive"))
    )
    (net (code "84") (name "Net-(U4A-XMP{slash}~{MC})") (class "Default")
      (node (ref "R32") (pin "2") (pinfunction "2_2") (pintype "passive"))
      (node (ref "U4") (pin "17") (pinfunction "XMP/~{MC}_17") (pintype "passive"))
    )
    (net (code "85") (name "Net-(U4A-~{XHOLD})") (class "Default")
      (node (ref "R31") (pin "2") (pinfunction "2_2") (pintype "passive"))
      (node (ref "U4") (pin "159") (pinfunction "~{XHOLD}_159") (pintype "passive"))
    )
    (net (code "86") (name "Net-(U4B-X1{slash}XCLKIN)") (class "Default")
      (node (ref "C43") (pin "1") (pinfunction "1_1") (pintype "passive"))
      (node (ref "U4") (pin "77") (pinfunction "X1/XCLKIN_77") (pintype "passive"))
      (node (ref "Y1") (pin "1") (pinfunction "OSC1_1") (pintype "passive"))
    )
    (net (code "87") (name "Net-(U4B-X2)") (class "Default")
      (node (ref "C42") (pin "1") (pinfunction "1_1") (pintype "passive"))
      (node (ref "U4") (pin "76") (pinfunction "X2_76") (pintype "passive"))
      (node (ref "Y1") (pin "2") (pinfunction "OSC2_2") (pintype "passive"))
    )
    (net (code "88") (name "Net-(U4B-XCLKOUT)") (class "Default")
      (node (ref "R30") (pin "1") (pinfunction "1_1") (pintype "passive"))
      (node (ref "U4") (pin "119") (pinfunction "XCLKOUT_119") (pintype "passive"))
    )
    (net (code "89") (name "Net-(U4F-GPIOF4{slash}SCITXDA)") (class "Default")
      (node (ref "R18") (pin "1") (pinfunction "1_1") (pintype "passive"))
      (node (ref "U4") (pin "155") (pinfunction "GPIOF4/SCITXDA_155") (pintype "passive"))
    )
    (net (code "90") (name "Net-(U4F-GPIOF14{slash}XF_~{XPLLDIS})") (class "Default")
      (node (ref "R15") (pin "2") (pinfunction "2_2") (pintype "passive"))
      (node (ref "U4") (pin "140") (pinfunction "GPIOF14/XF_~{XPLLDIS}_140") (pintype "passive"))
    )
    (net (code "91") (name "Net-(U5-1A1)") (class "Default")
      (node (ref "R13") (pin "1") (pinfunction "1_1") (pintype "passive"))
      (node (ref "U5") (pin "4") (pinfunction "1A1_4") (pintype "passive"))
    )
    (net (code "92") (name "Net-(U5-1A2)") (class "Default")
      (node (ref "R16") (pin "1") (pinfunction "1_1") (pintype "passive"))
      (node (ref "U5") (pin "6") (pinfunction "1A2_6") (pintype "passive"))
    )
    (net (code "93") (name "Net-(U5-1A3)") (class "Default")
      (node (ref "R19") (pin "1") (pinfunction "1_1") (pintype "passive"))
      (node (ref "U5") (pin "8") (pinfunction "1A3_8") (pintype "passive"))
    )
    (net (code "94") (name "Net-(U5-1Y0)") (class "Default")
      (node (ref "R12") (pin "2") (pinfunction "2_2") (pintype "passive"))
      (node (ref "U5") (pin "18") (pinfunction "1Y0_18") (pintype "passive"))
    )
    (net (code "95") (name "Net-(U5-1Y1)") (class "Default")
      (node (ref "R14") (pin "2") (pinfunction "2_2") (pintype "passive"))
      (node (ref "U5") (pin "16") (pinfunction "1Y1_16") (pintype "passive"))
    )
    (net (code "96") (name "Net-(U5-1Y2)") (class "Default")
      (node (ref "R17") (pin "2") (pinfunction "2_2") (pintype "passive"))
      (node (ref "U5") (pin "14") (pinfunction "1Y2_14") (pintype "passive"))
    )
    (net (code "97") (name "Net-(U5-1Y3)") (class "Default")
      (node (ref "R20") (pin "2") (pinfunction "2_2") (pintype "passive"))
      (node (ref "U5") (pin "12") (pinfunction "1Y3_12") (pintype "passive"))
    )
    (net (code "98") (name "Net-(U5-2A0)") (class "Default")
      (node (ref "R21") (pin "1") (pinfunction "1_1") (pintype "passive"))
      (node (ref "U5") (pin "17") (pinfunction "2A0_17") (pintype "passive"))
    )
    (net (code "99") (name "Net-(U5-2A1)") (class "Default")
      (node (ref "R23") (pin "1") (pinfunction "1_1") (pintype "passive"))
      (node (ref "U5") (pin "15") (pinfunction "2A1_15") (pintype "passive"))
    )
    (net (code "100") (name "Net-(U5-2A2)") (class "Default")
      (node (ref "R25") (pin "1") (pinfunction "1_1") (pintype "passive"))
      (node (ref "U5") (pin "13") (pinfunction "2A2_13") (pintype "passive"))
    )
    (net (code "101") (name "Net-(U5-2Y0)") (class "Default")
      (node (ref "R22") (pin "2") (pinfunction "2_2") (pintype "passive"))
      (node (ref "U5") (pin "3") (pinfunction "2Y0_3") (pintype "passive"))
    )
    (net (code "102") (name "Net-(U5-2Y1)") (class "Default")
      (node (ref "R24") (pin "2") (pinfunction "2_2") (pintype "passive"))
      (node (ref "U5") (pin "5") (pinfunction "2Y1_5") (pintype "passive"))
    )
    (net (code "103") (name "Net-(U5-2Y2)") (class "Default")
      (node (ref "R26") (pin "2") (pinfunction "2_2") (pintype "passive"))
      (node (ref "U5") (pin "7") (pinfunction "2Y2_7") (pintype "passive"))
    )
    (net (code "104") (name "Net-(U5-2Y3)") (class "Default")
      (node (ref "R27") (pin "2") (pinfunction "2_2") (pintype "passive"))
      (node (ref "U5") (pin "9") (pinfunction "2Y3_9") (pintype "passive"))
    )
    (net (code "105") (name "unconnected-(U4A-XREADY-Pad161)") (class "Default")
      (node (ref "U4") (pin "161") (pinfunction "XREADY_161") (pintype "passive+no_connect"))
    )
    (net (code "106") (name "unconnected-(U4A-~{XHOLDA}-Pad82)") (class "Default")
      (node (ref "U4") (pin "82") (pinfunction "~{XHOLDA}_82") (pintype "passive+no_connect"))
    )
    (net (code "107") (name "unconnected-(U4B-TEST1-Pad67)") (class "Default")
      (node (ref "U4") (pin "67") (pinfunction "TEST1_67") (pintype "passive+no_connect"))
    )
    (net (code "108") (name "unconnected-(U4B-TEST2-Pad66)") (class "Default")
      (node (ref "U4") (pin "66") (pinfunction "TEST2_66") (pintype "passive+no_connect"))
    )
    (net (code "109") (name "unconnected-(U4D-AVDDREFBG-Pad13)") (class "Default")
      (node (ref "U4") (pin "13") (pinfunction "AVDDREFBG_13") (pintype "passive"))
    )
    (net (code "110") (name "unconnected-(U4D-AVSSREFBG-Pad12)") (class "Default")
      (node (ref "U4") (pin "12") (pinfunction "AVSSREFBG_12") (pintype "passive"))
    )
    (net (code "111") (name "unconnected-(U4D-VDD1-Pad162)") (class "Default")
      (node (ref "U4") (pin "162") (pinfunction "VDD1_162") (pintype "passive"))
    )
    (net (code "112") (name "unconnected-(U4D-VDDA1-Pad14)") (class "Default")
      (node (ref "U4") (pin "14") (pinfunction "VDDA1_14") (pintype "passive"))
    )
    (net (code "113") (name "unconnected-(U4D-VDDA2-Pad166)") (class "Default")
      (node (ref "U4") (pin "166") (pinfunction "VDDA2_166") (pintype "passive"))
    )
    (net (code "114") (name "unconnected-(U4D-VDDA_IO-Pad1)") (class "Default")
      (node (ref "U4") (pin "1") (pinfunction "VDDA_IO_1") (pintype "power_in"))
    )
    (net (code "115") (name "unconnected-(U4D-VSS1-Pad163)") (class "Default")
      (node (ref "U4") (pin "163") (pinfunction "VSS1_163") (pintype "passive"))
    )
    (net (code "116") (name "unconnected-(U4D-VSSA1-Pad15)") (class "Default")
      (node (ref "U4") (pin "15") (pinfunction "VSSA1_15") (pintype "passive"))
    )
    (net (code "117") (name "unconnected-(U4D-VSSA2-Pad165)") (class "Default")
      (node (ref "U4") (pin "165") (pinfunction "VSSA2_165") (pintype "passive"))
    )
    (net (code "118") (name "unconnected-(U4D-VSSAIO-Pad176)") (class "Default")
      (node (ref "U4") (pin "176") (pinfunction "VSSAIO_176") (pintype "passive"))
    )
    (net (code "119") (name "unconnected-(U4E-GPIOA0{slash}PWM1-Pad92)") (class "Default")
      (node (ref "U4") (pin "92") (pinfunction "GPIOA0/PWM1_92") (pintype "passive+no_connect"))
    )
    (net (code "120") (name "unconnected-(U4E-GPIOA1{slash}PWM2-Pad93)") (class "Default")
      (node (ref "U4") (pin "93") (pinfunction "GPIOA1/PWM2_93") (pintype "passive+no_connect"))
    )
    (net (code "121") (name "unconnected-(U4E-GPIOA4{slash}PWM5-Pad98)") (class "Default")
      (node (ref "U4") (pin "98") (pinfunction "GPIOA4/PWM5_98") (pintype "passive+no_connect"))
    )
    (net (code "122") (name "unconnected-(U4E-GPIOA5{slash}PWM6-Pad101)") (class "Default")
      (node (ref "U4") (pin "101") (pinfunction "GPIOA5/PWM6_101") (pintype "passive+no_connect"))
    )
    (net (code "123") (name "unconnected-(U4E-GPIOA6{slash}T1PWM_T1CMP-Pad102)") (class "Default")
      (node (ref "U4") (pin "102") (pinfunction "GPIOA6/T1PWM_T1CMP_102") (pintype "passive+no_connect"))
    )
    (net (code "124") (name "unconnected-(U4E-GPIOA7{slash}T2PWM_T2CMP-Pad104)") (class "Default")
      (node (ref "U4") (pin "104") (pinfunction "GPIOA7/T2PWM_T2CMP_104") (pintype "passive+no_connect"))
    )
    (net (code "125") (name "unconnected-(U4E-GPIOA8{slash}CAP1_QEP1-Pad106)") (class "Default")
      (node (ref "U4") (pin "106") (pinfunction "GPIOA8/CAP1_QEP1_106") (pintype "passive+no_connect"))
    )
    (net (code "126") (name "unconnected-(U4E-GPIOA9{slash}CAP2_QEP2-Pad107)") (class "Default")
      (node (ref "U4") (pin "107") (pinfunction "GPIOA9/CAP2_QEP2_107") (pintype "passive+no_connect"))
    )
    (net (code "127") (name "unconnected-(U4E-GPIOA10{slash}CAP3_QEPI1-Pad109)") (class "Default")
      (node (ref "U4") (pin "109") (pinfunction "GPIOA10/CAP3_QEPI1_109") (pintype "passive+no_connect"))
    )
    (net (code "128") (name "unconnected-(U4E-GPIOA11{slash}TDIRA-Pad116)") (class "Default")
      (node (ref "U4") (pin "116") (pinfunction "GPIOA11/TDIRA_116") (pintype "passive+no_connect"))
    )
    (net (code "129") (name "unconnected-(U4E-GPIOA12{slash}TCLKINA-Pad117)") (class "Default")
      (node (ref "U4") (pin "117") (pinfunction "GPIOA12/TCLKINA_117") (pintype "passive+no_connect"))
    )
    (net (code "130") (name "unconnected-(U4E-GPIOA13{slash}~{C1TRIP}-Pad122)") (class "Default")
      (node (ref "U4") (pin "122") (pinfunction "GPIOA13/~{C1TRIP}_122") (pintype "passive+no_connect"))
    )
    (net (code "131") (name "unconnected-(U4E-GPIOA14{slash}~{C2TRIP}-Pad123)") (class "Default")
      (node (ref "U4") (pin "123") (pinfunction "GPIOA14/~{C2TRIP}_123") (pintype "passive+no_connect"))
    )
    (net (code "132") (name "unconnected-(U4E-GPIOA15{slash}~{C3TRIP}-Pad124)") (class "Default")
      (node (ref "U4") (pin "124") (pinfunction "GPIOA15/~{C3TRIP}_124") (pintype "passive+no_connect"))
    )
    (net (code "133") (name "unconnected-(U4E-GPIOB0{slash}PWM7-Pad45)") (class "Default")
      (node (ref "U4") (pin "45") (pinfunction "GPIOB0/PWM7_45") (pintype "passive+no_connect"))
    )
    (net (code "134") (name "unconnected-(U4E-GPIOB1{slash}PWM8-Pad46)") (class "Default")
      (node (ref "U4") (pin "46") (pinfunction "GPIOB1/PWM8_46") (pintype "passive+no_connect"))
    )
    (net (code "135") (name "unconnected-(U4E-GPIOB3{slash}PWM10-Pad48)") (class "Default")
      (node (ref "U4") (pin "48") (pinfunction "GPIOB3/PWM10_48") (pintype "passive+no_connect"))
    )
    (net (code "136") (name "unconnected-(U4E-GPIOB4{slash}PWM11-Pad49)") (class "Default")
      (node (ref "U4") (pin "49") (pinfunction "GPIOB4/PWM11_49") (pintype "passive+no_connect"))
    )
    (net (code "137") (name "unconnected-(U4E-GPIOB5{slash}PWM12-Pad50)") (class "Default")
      (node (ref "U4") (pin "50") (pinfunction "GPIOB5/PWM12_50") (pintype "passive+no_connect"))
    )
    (net (code "138") (name "unconnected-(U4E-GPIOB6{slash}T3PWM_T3CMP-Pad53)") (class "Default")
      (node (ref "U4") (pin "53") (pinfunction "GPIOB6/T3PWM_T3CMP_53") (pintype "passive+no_connect"))
    )
    (net (code "139") (name "unconnected-(U4E-GPIOB7{slash}T4PWM_T4CMP-Pad55)") (class "Default")
      (node (ref "U4") (pin "55") (pinfunction "GPIOB7/T4PWM_T4CMP_55") (pintype "passive+no_connect"))
    )
    (net (code "140") (name "unconnected-(U4E-GPIOB8{slash}CMP4_QEP3-Pad57)") (class "Default")
      (node (ref "U4") (pin "57") (pinfunction "GPIOB8/CMP4_QEP3_57") (pintype "passive+no_connect"))
    )
    (net (code "141") (name "unconnected-(U4E-GPIOB11{slash}TDIRB-Pad71)") (class "Default")
      (node (ref "U4") (pin "71") (pinfunction "GPIOB11/TDIRB_71") (pintype "passive+no_connect"))
    )
    (net (code "142") (name "unconnected-(U4E-GPIOB12{slash}TCLKINB-Pad72)") (class "Default")
      (node (ref "U4") (pin "72") (pinfunction "GPIOB12/TCLKINB_72") (pintype "passive+no_connect"))
    )
    (net (code "143") (name "unconnected-(U4F-GPIOD0{slash}~{T1CTRIP}_~{PDPINTA}-Pad110)") (class "Default")
      (node (ref "U4") (pin "110") (pinfunction "GPIOD0/~{T1CTRIP}_~{PDPINTA}_110") (pintype "passive+no_connect"))
    )
    (net (code "144") (name "unconnected-(U4F-GPIOD1{slash}~{T2CTRIP}_~{EVASOC}-Pad115)") (class "Default")
      (node (ref "U4") (pin "115") (pinfunction "GPIOD1/~{T2CTRIP}_~{EVASOC}_115") (pintype "passive+no_connect"))
    )
    (net (code "145") (name "unconnected-(U4F-GPIOD5{slash}~{T3CTRIP}_~{PDPINTB}-Pad79)") (class "Default")
      (node (ref "U4") (pin "79") (pinfunction "GPIOD5/~{T3CTRIP}_~{PDPINTB}_79") (pintype "passive+no_connect"))
    )
    (net (code "146") (name "unconnected-(U4F-GPIOD6{slash}~{T4CTRIP}_~{EVBSOC}-Pad83)") (class "Default")
      (node (ref "U4") (pin "83") (pinfunction "GPIOD6/~{T4CTRIP}_~{EVBSOC}_83") (pintype "passive+no_connect"))
    )
    (net (code "147") (name "unconnected-(U4F-GPIOF0{slash}SPISIMOA-Pad40)") (class "Default")
      (node (ref "U4") (pin "40") (pinfunction "GPIOF0/SPISIMOA_40") (pintype "passive+no_connect"))
    )
    (net (code "148") (name "unconnected-(U4F-GPIOF1{slash}SPISOMIA-Pad41)") (class "Default")
      (node (ref "U4") (pin "41") (pinfunction "GPIOF1/SPISOMIA_41") (pintype "passive+no_connect"))
    )
    (net (code "149") (name "unconnected-(U4F-GPIOF2{slash}SPICLKA-Pad34)") (class "Default")
      (node (ref "U4") (pin "34") (pinfunction "GPIOF2/SPICLKA_34") (pintype "passive+no_connect"))
    )
    (net (code "150") (name "unconnected-(U4F-GPIOF3{slash}SPISTEA-Pad35)") (class "Default")
      (node (ref "U4") (pin "35") (pinfunction "GPIOF3/SPISTEA_35") (pintype "passive+no_connect"))
    )
    (net (code "151") (name "unconnected-(U4F-GPIOF5{slash}SCIRXDA-Pad157)") (class "Default")
      (node (ref "U4") (pin "157") (pinfunction "GPIOF5/SCIRXDA_157") (pintype "passive+no_connect"))
    )
    (net (code "152") (name "unconnected-(U4F-GPIOF6{slash}CANTXA-Pad87)") (class "Default")
      (node (ref "U4") (pin "87") (pinfunction "GPIOF6/CANTXA_87") (pintype "passive+no_connect"))
    )
    (net (code "153") (name "unconnected-(U4F-GPIOF7{slash}CANRXA-Pad89)") (class "Default")
      (node (ref "U4") (pin "89") (pinfunction "GPIOF7/CANRXA_89") (pintype "passive+no_connect"))
    )
    (net (code "154") (name "unconnected-(U5-1A0-Pad2)") (class "Default")
      (node (ref "U5") (pin "2") (pinfunction "1A0_2") (pintype "passive+no_connect"))
    )
    (net (code "155") (name "unconnected-(U5-2A3-Pad11)") (class "Default")
      (node (ref "U5") (pin "11") (pinfunction "2A3_11") (pintype "passive+no_connect"))
    )
    (net (code "156") (name "unconnected-(U7-INA-Pad1)") (class "Default")
      (node (ref "U7") (pin "1") (pinfunction "INA_1") (pintype "passive"))
    )
    (net (code "157") (name "unconnected-(U7-INB-Pad7)") (class "Default")
      (node (ref "U7") (pin "7") (pinfunction "INB_7") (pintype "passive"))
    )
    (net (code "158") (name "unconnected-(U7-OUTA1-Pad3)") (class "Default")
      (node (ref "U7") (pin "3") (pinfunction "OUTA1_3") (pintype "passive"))
    )
    (net (code "159") (name "unconnected-(U7-OUTA2-Pad2)") (class "Default")
      (node (ref "U7") (pin "2") (pinfunction "OUTA2_2") (pintype "passive"))
    )
    (net (code "160") (name "unconnected-(U7-OUTB1-Pad5)") (class "Default")
      (node (ref "U7") (pin "5") (pinfunction "OUTB1_5") (pintype "passive"))
    )
    (net (code "161") (name "unconnected-(U7-OUTB2-Pad6)") (class "Default")
      (node (ref "U7") (pin "6") (pinfunction "OUTB2_6") (pintype "passive"))
    )
    (net (code "162") (name "unconnected-(U7-OUTD1-Pad13)") (class "Default")
      (node (ref "U7") (pin "13") (pinfunction "OUTD1_13") (pintype "passive+no_connect"))
    )
    (net (code "163") (name "unconnected-(U7-OUTD2-Pad14)") (class "Default")
      (node (ref "U7") (pin "14") (pinfunction "OUTD2_14") (pintype "passive+no_connect"))
    )
  )
)
